# WirelessI2cController.net
KiCad netlist of a schematic drawn in EAGLE
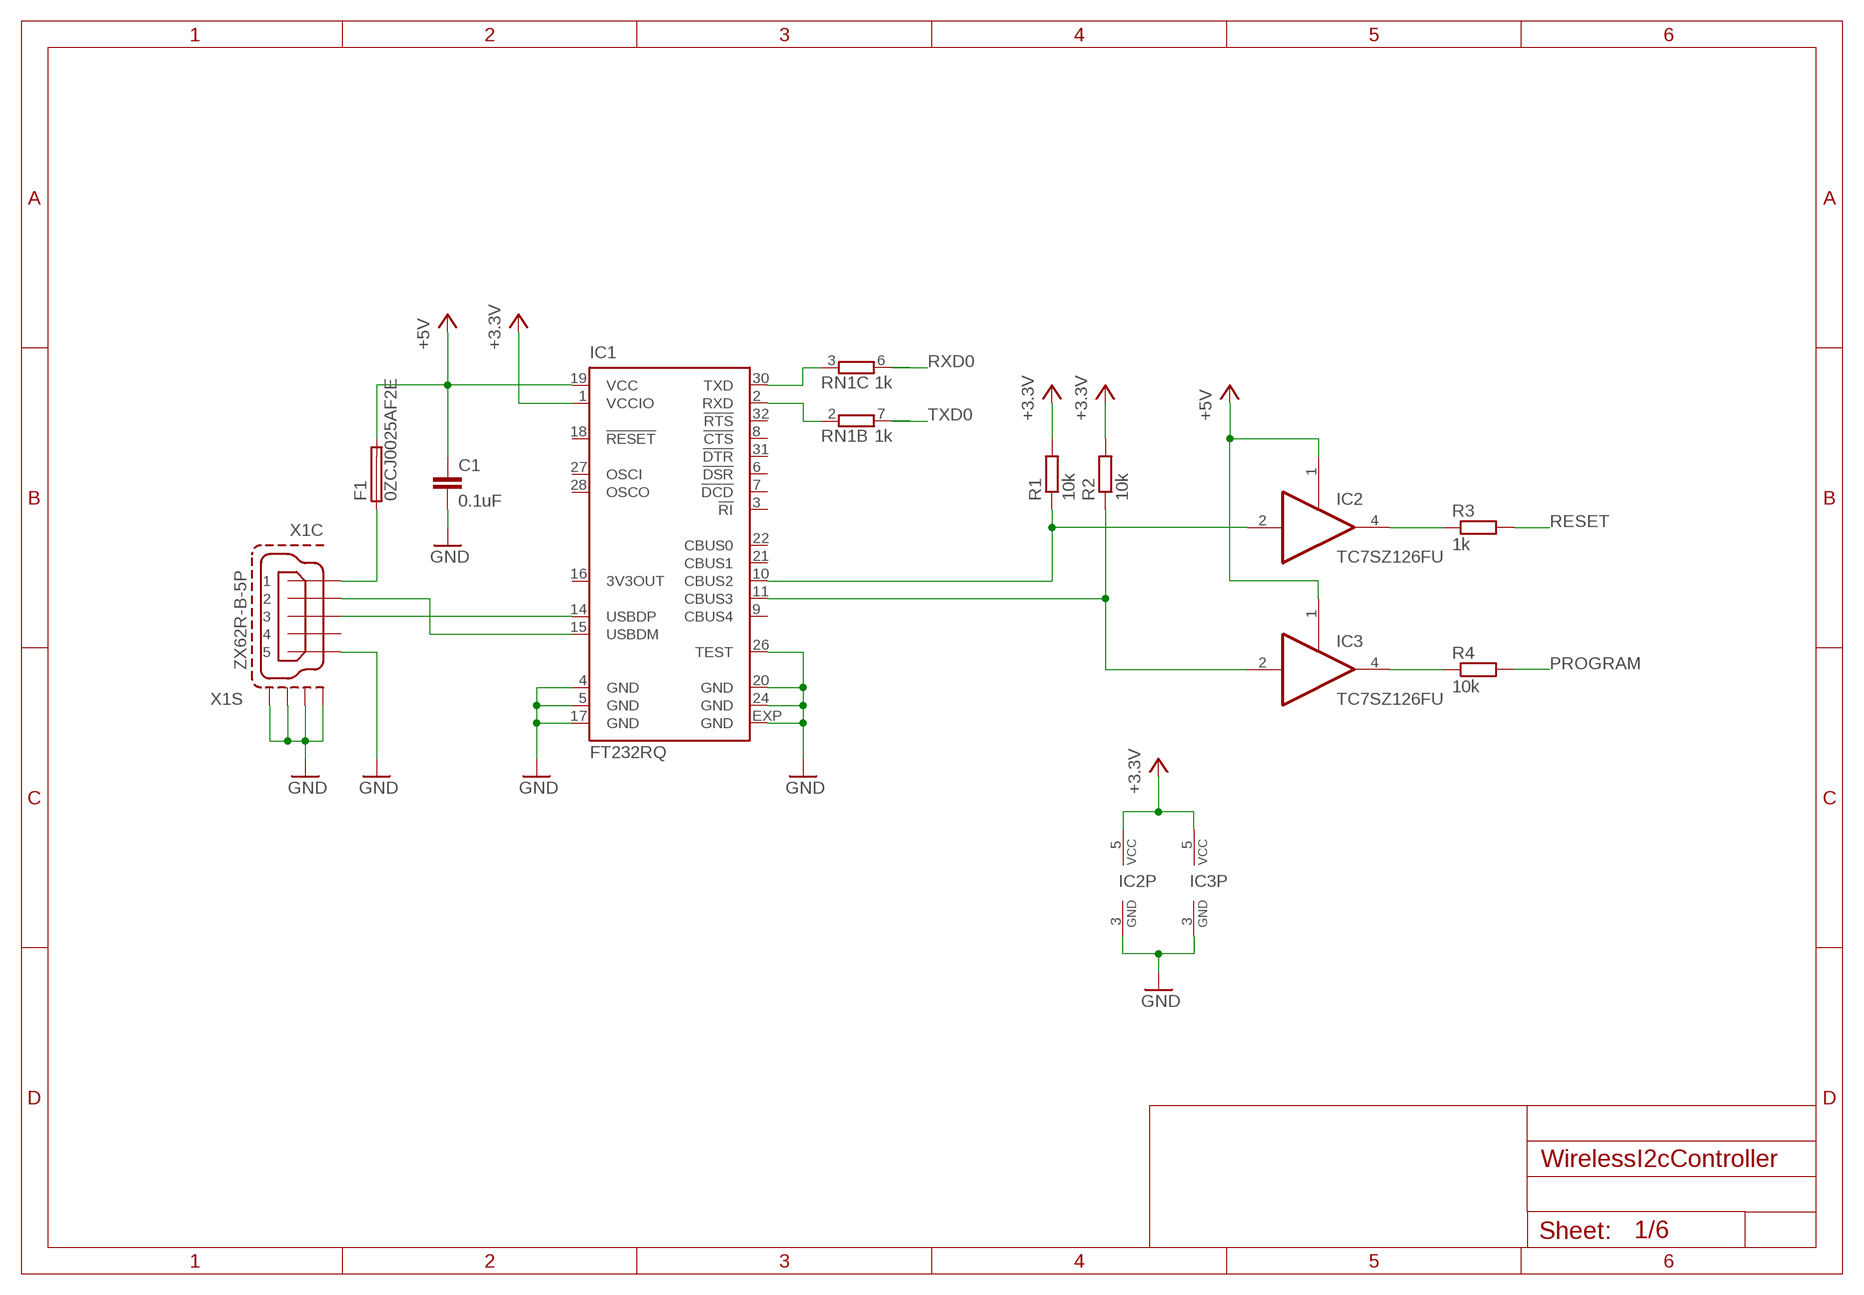
[diagram p0: schematic, sheet 1]
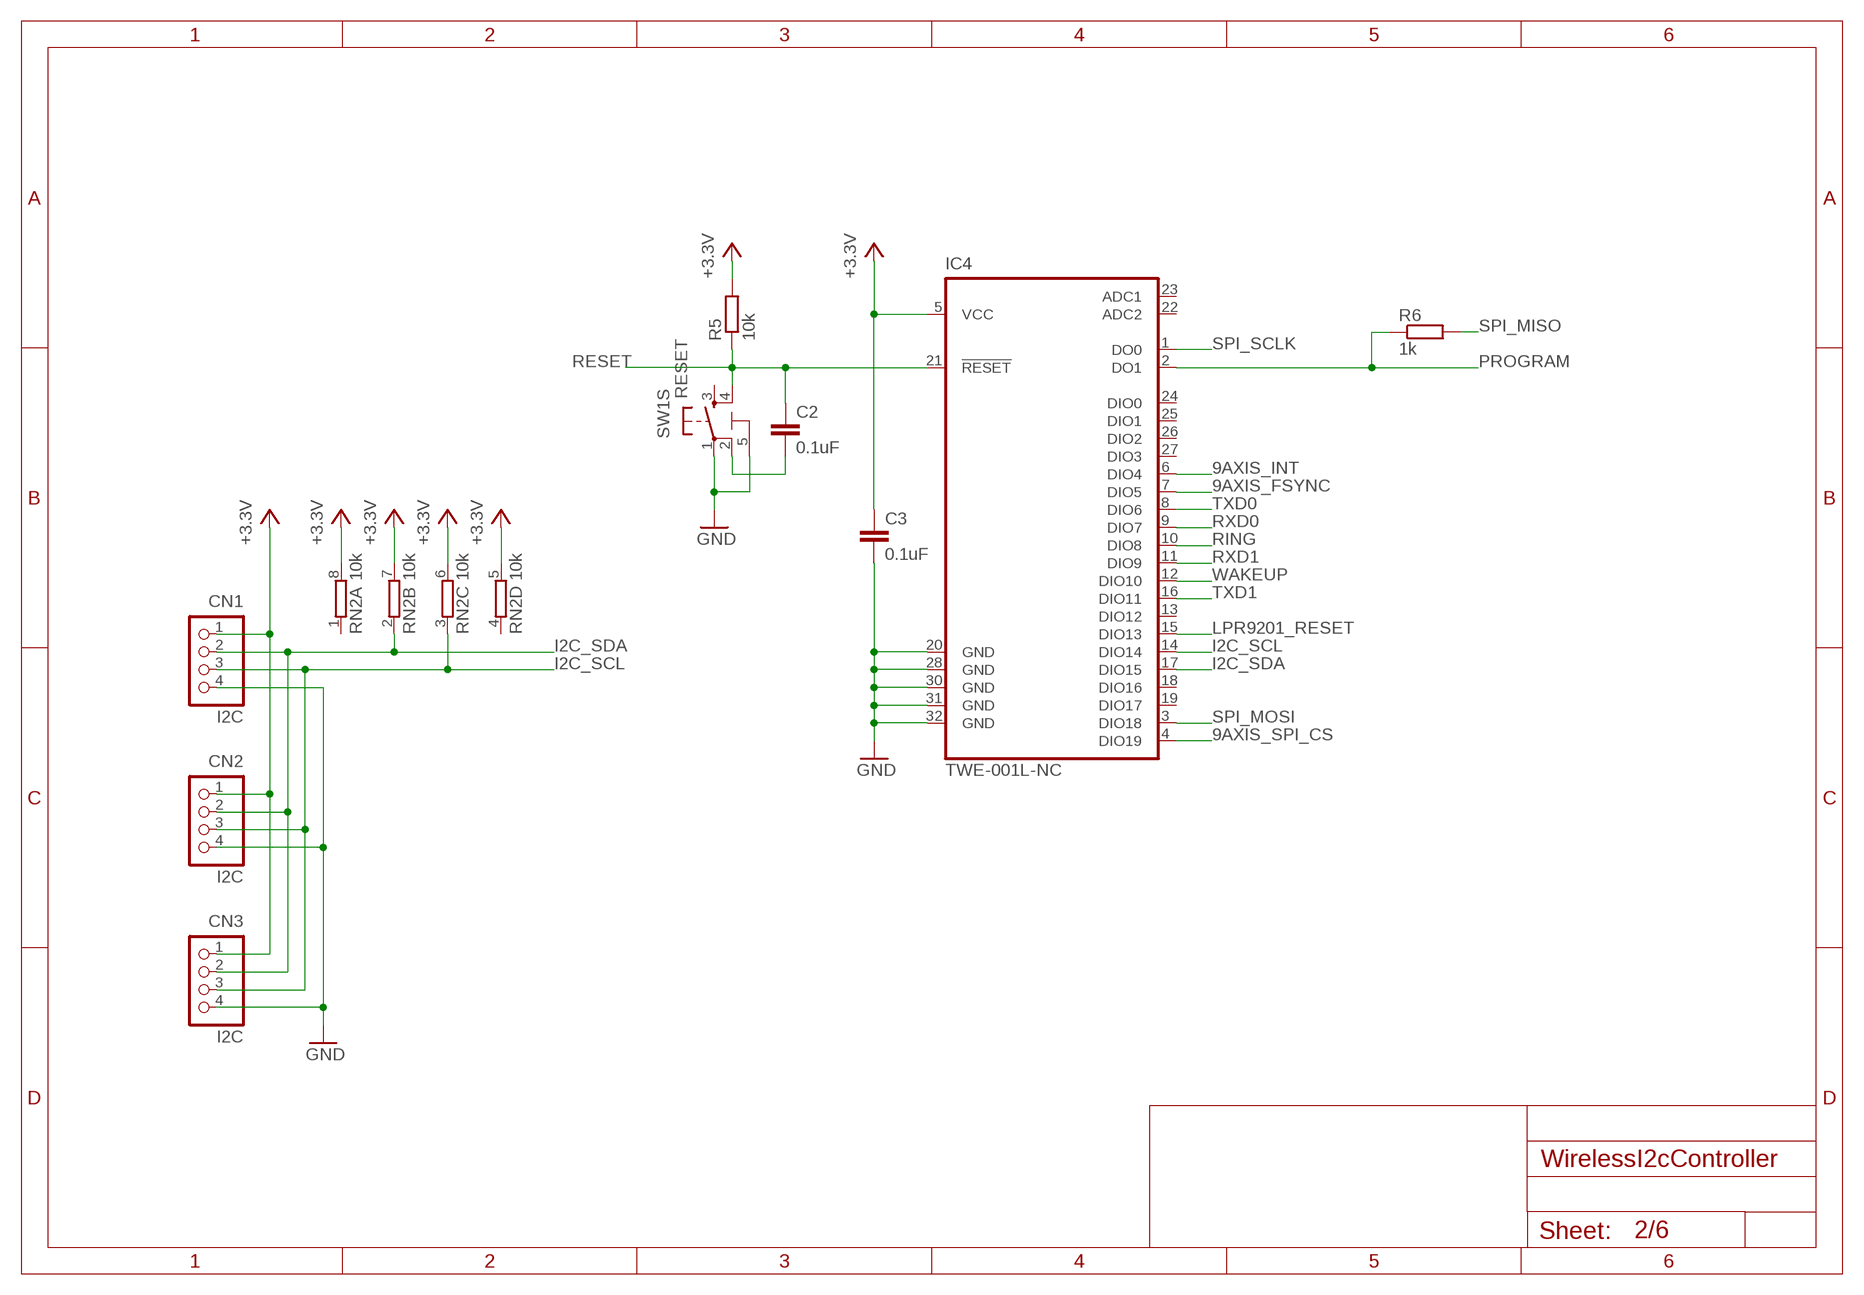
[diagram p1: schematic, sheet 2]
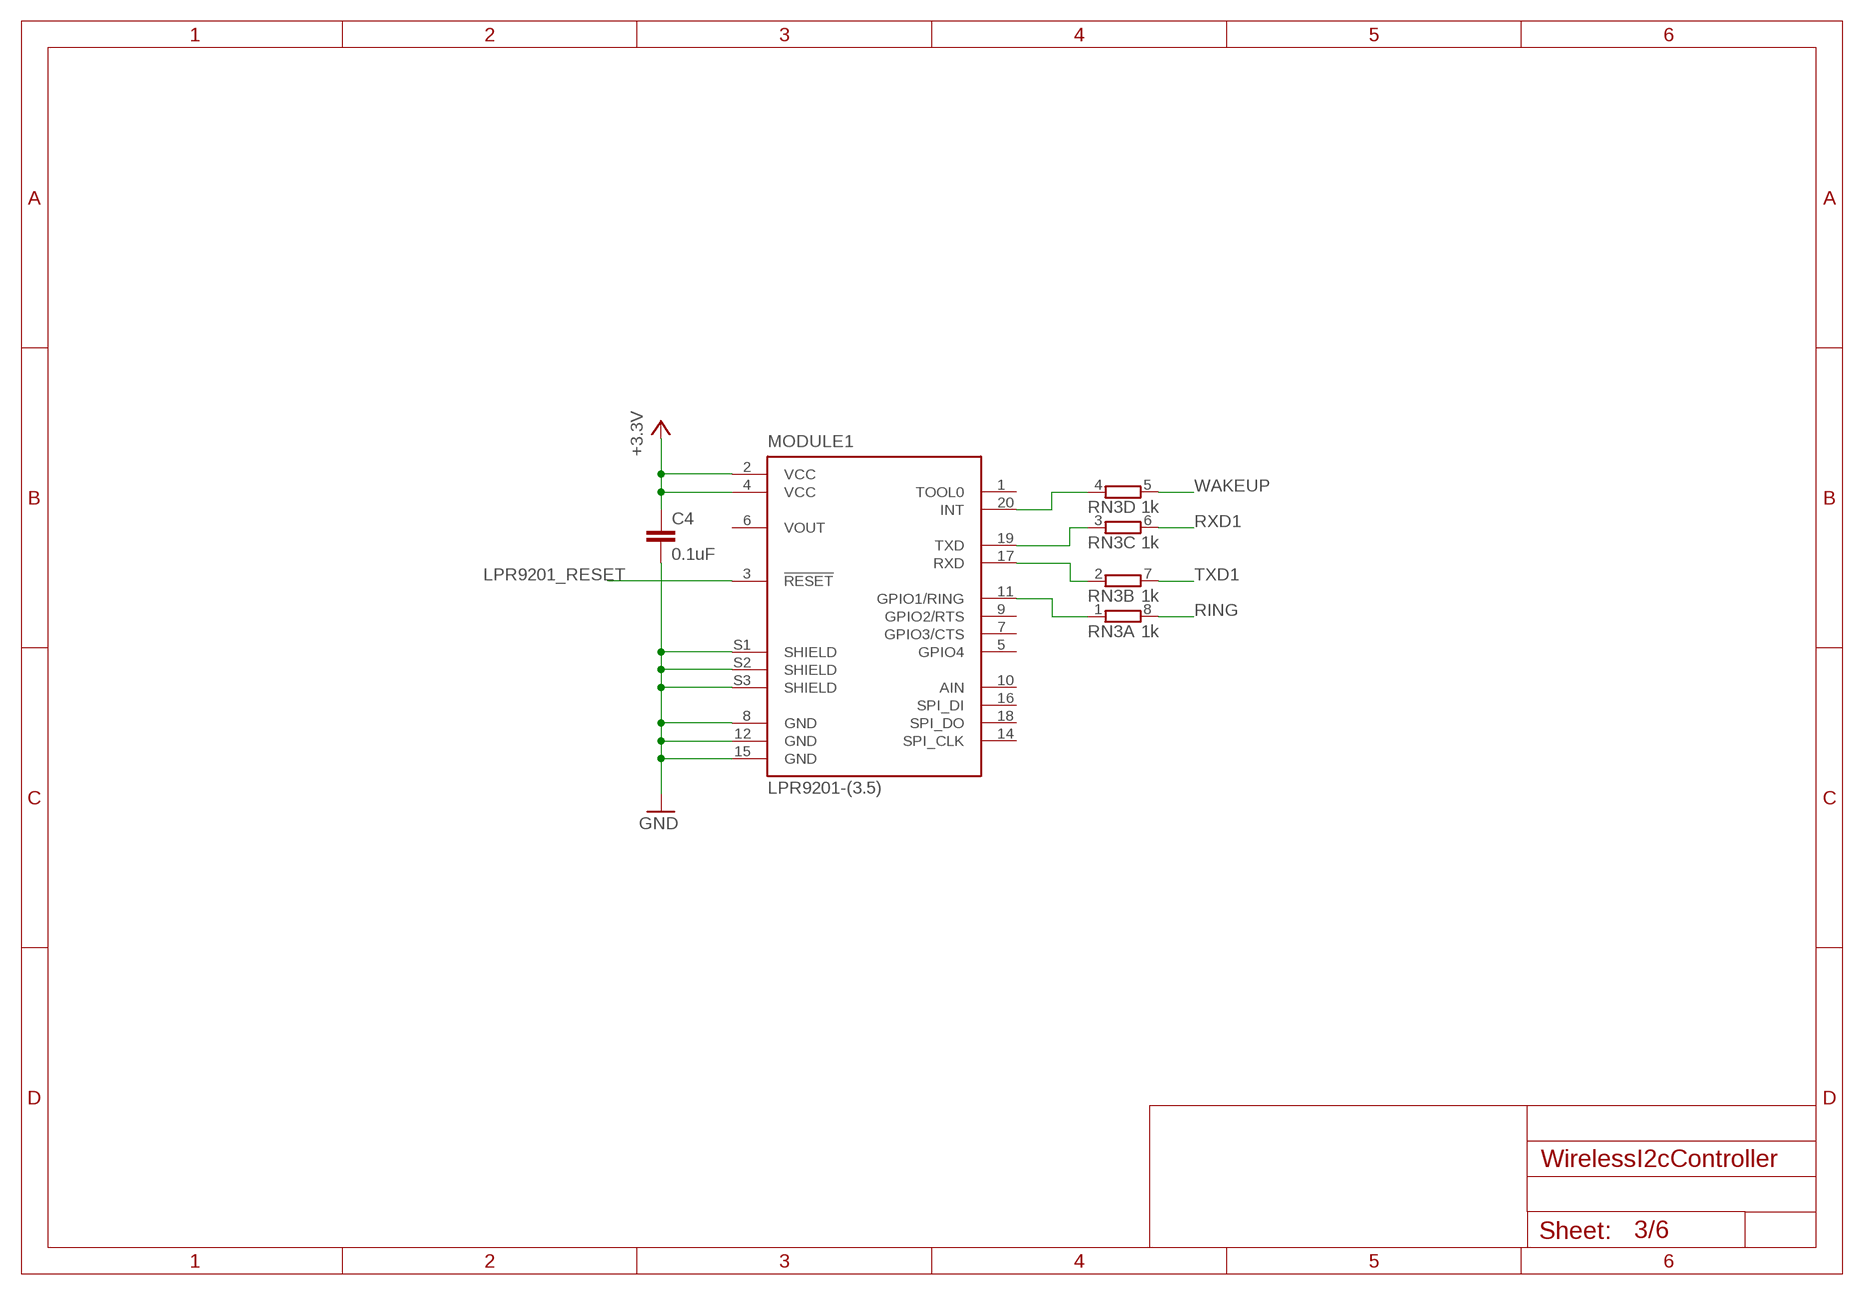
[diagram p2: schematic, sheet 3]
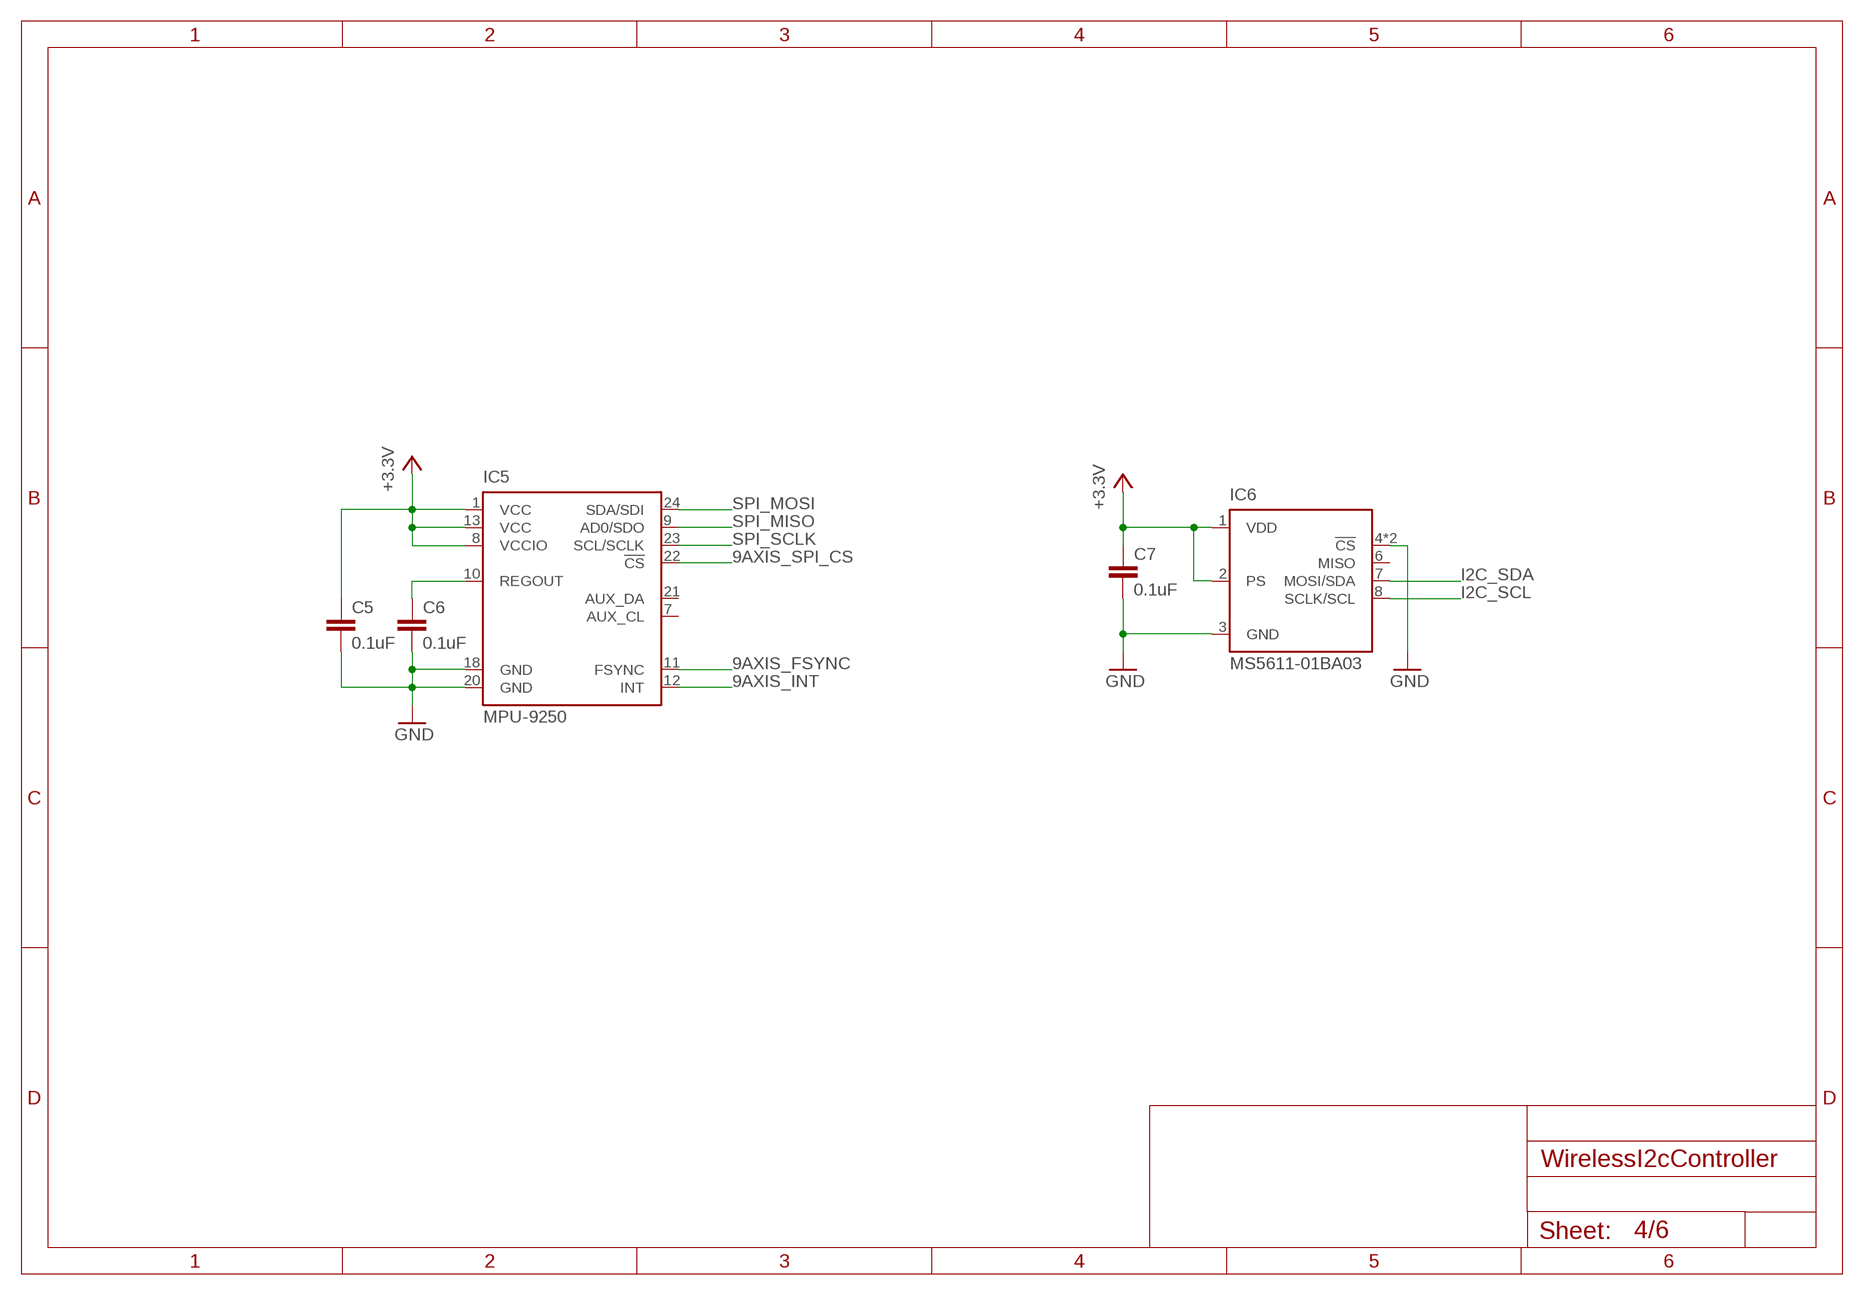
[diagram p3: schematic, sheet 4]
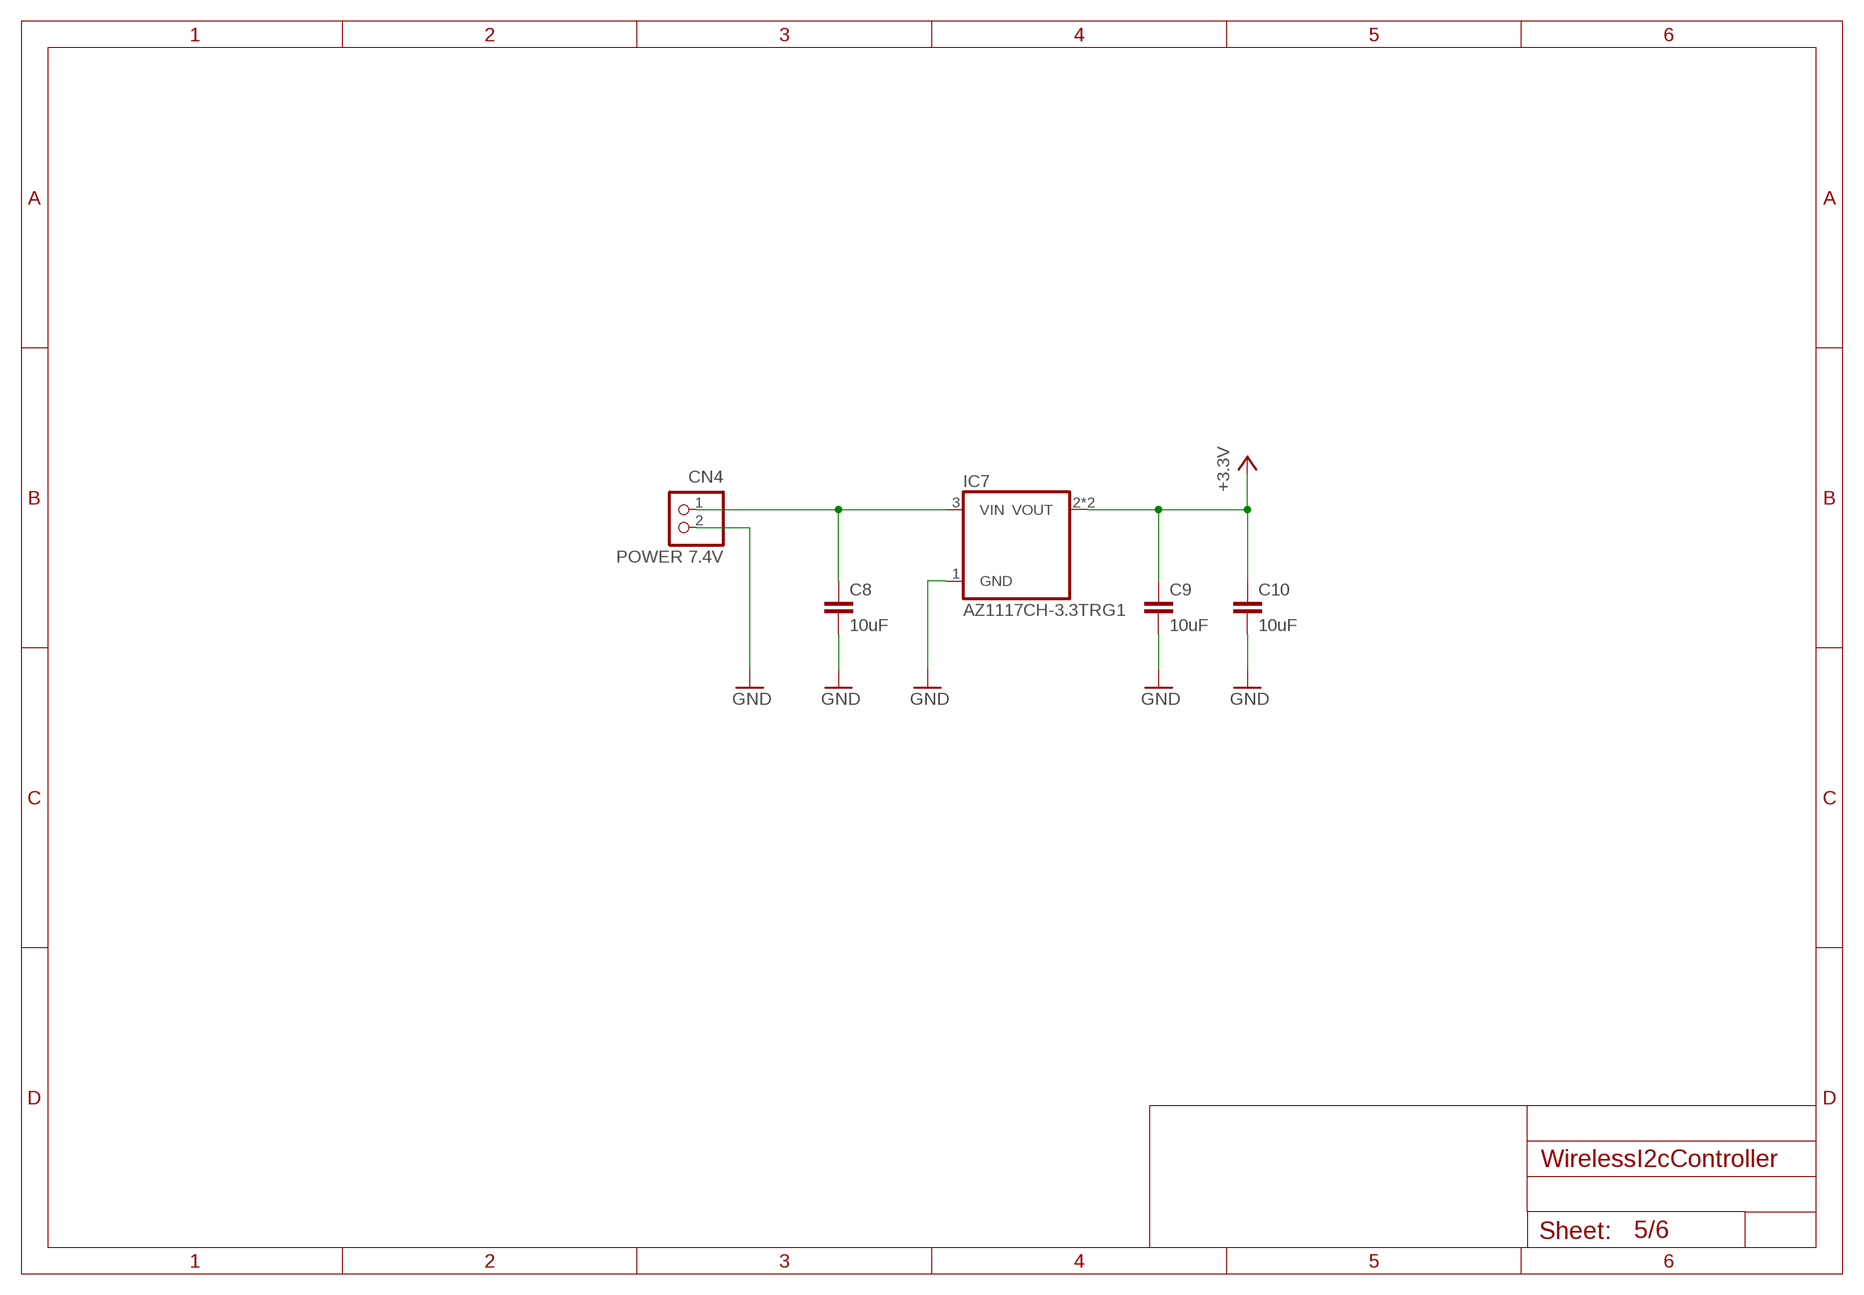
[diagram p4: schematic, sheet 5]
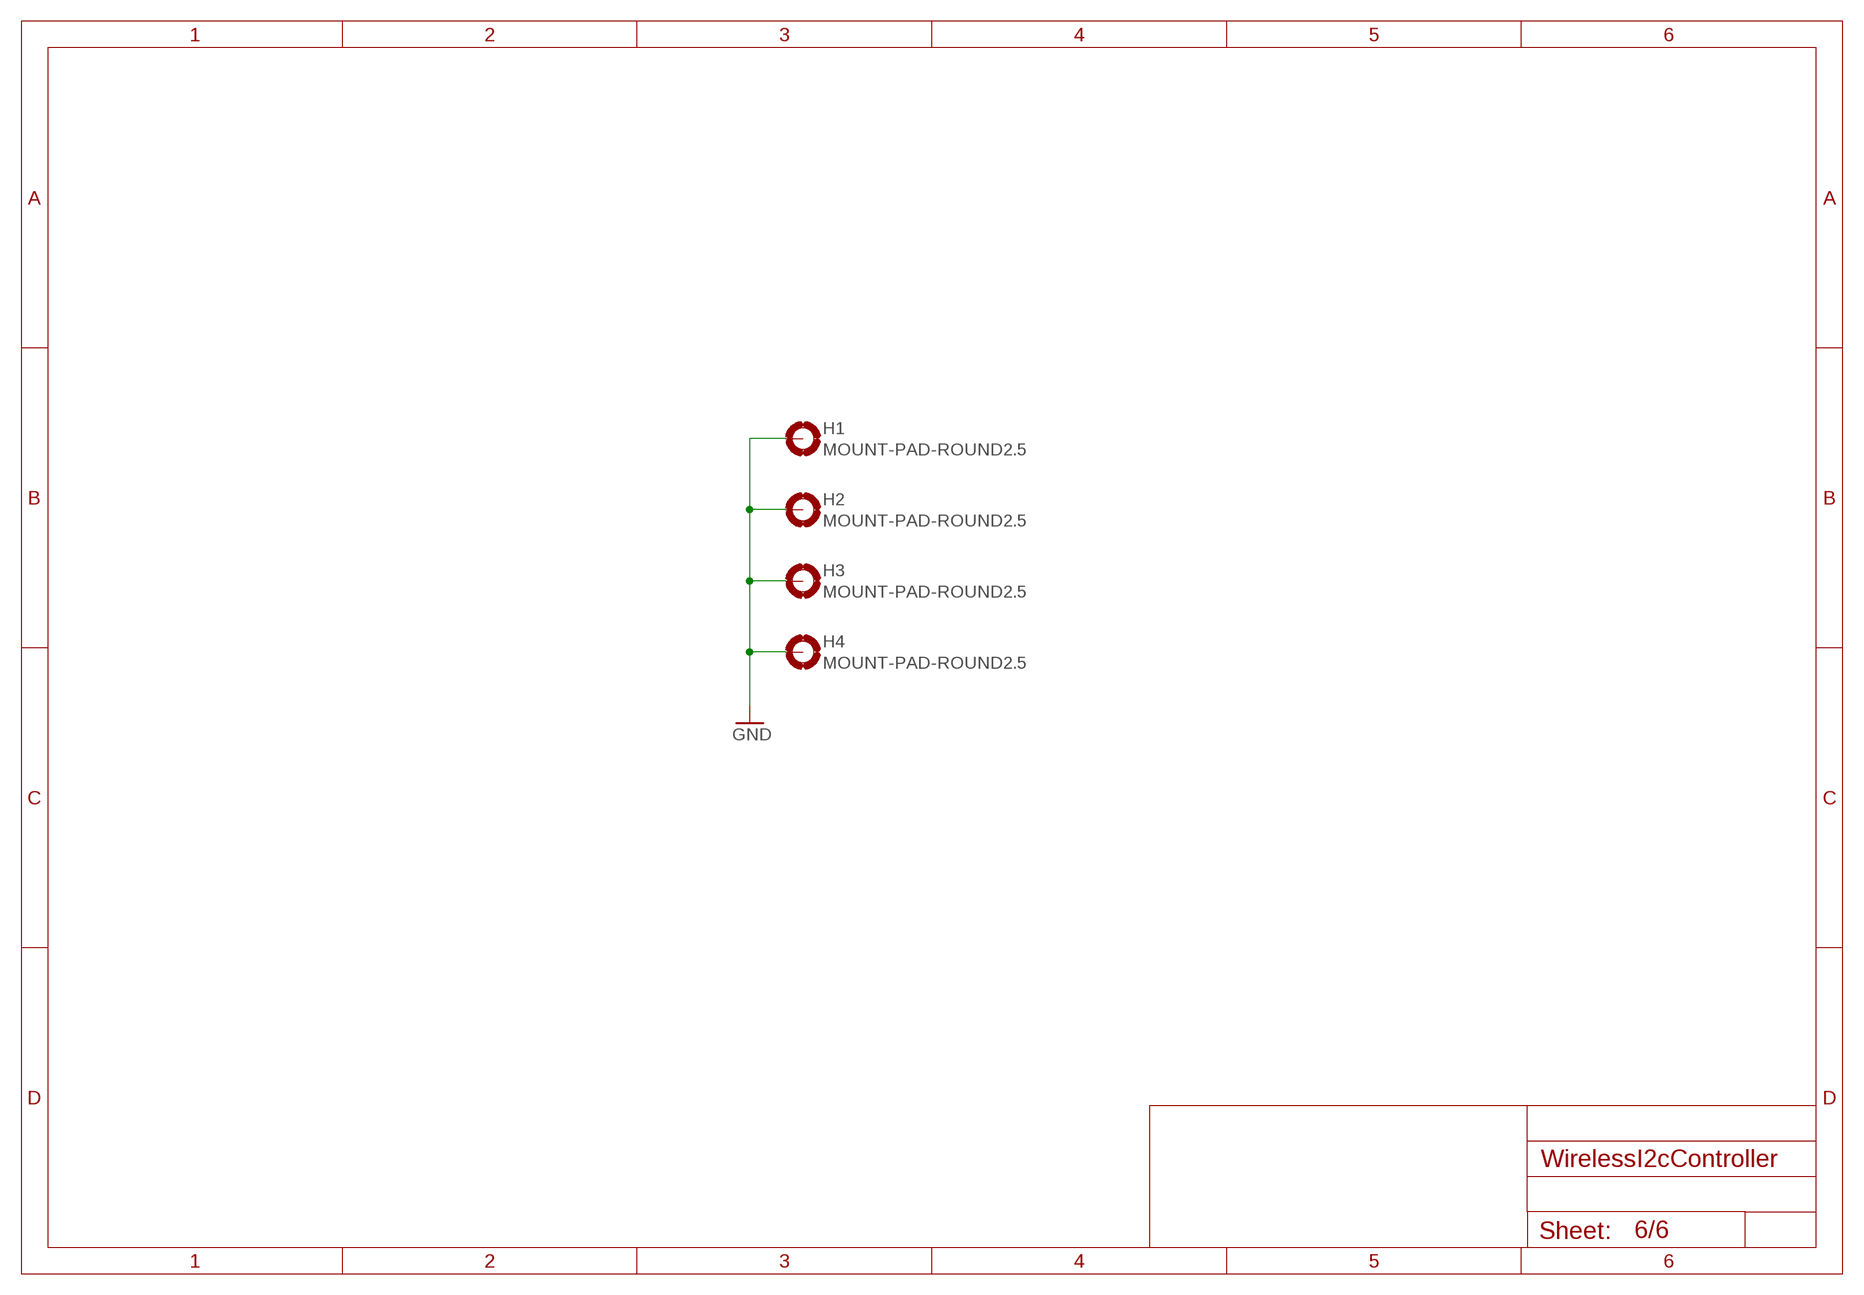
[diagram p5: schematic, sheet 6]

(export (version "E")
  (design (tool "Eeschema 10.0.6"))
  (components
    (comp (ref "C5")
      (value "0.1uF")
      (footprint "eagle-import:C0402")
      (libsource (lib "eagle-import") (part "C-EUC0402"))
    )
    (comp (ref "C6")
      (value "0.1uF")
      (footprint "eagle-import:C0402")
      (libsource (lib "eagle-import") (part "C-EUC0402"))
    )
    (comp (ref "C7")
      (value "0.1uF")
      (footprint "eagle-import:C0402")
      (libsource (lib "eagle-import") (part "C-EUC0402"))
    )
    (comp (ref "IC5")
      (value "MPU-9250")
      (footprint "eagle-import:QFN24-SMALL")
      (libsource (lib "eagle-import") (part "MPU-9250"))
    )
    (comp (ref "IC6")
      (value "MS5611-01BA03")
      (footprint "eagle-import:LGA8")
      (libsource (lib "eagle-import") (part "MS5611-01BA03"))
    )
    (comp (ref "C4")
      (value "0.1uF")
      (footprint "eagle-import:C0402")
      (libsource (lib "eagle-import") (part "C-EUC0402"))
    )
    (comp (ref "MODULE1")
      (value "LPR9201-(3.5)")
      (footprint "eagle-import:DF12(_)-20DP-0.5V")
      (libsource (lib "eagle-import") (part "LPR9201-()3.5"))
    )
    (comp (ref "RN3")
      (value "1k")
      (footprint "eagle-import:EXB38V")
      (libsource (lib "eagle-import") (part "4R-NEXB38V"))
    )
    (comp (ref "C8")
      (value "10uF")
      (footprint "eagle-import:C0805")
      (libsource (lib "eagle-import") (part "C-EUC0805"))
    )
    (comp (ref "C9")
      (value "10uF")
      (footprint "eagle-import:C0805")
      (libsource (lib "eagle-import") (part "C-EUC0805"))
    )
    (comp (ref "C10")
      (value "10uF")
      (footprint "eagle-import:C0805")
      (libsource (lib "eagle-import") (part "C-EUC0805"))
    )
    (comp (ref "CN4")
      (value "POWER 7.4V")
      (footprint "eagle-import:S2B-PH-K-S")
      (libsource (lib "eagle-import") (part "S2B-PH-K-S"))
    )
    (comp (ref "IC7")
      (value "AZ1117CH-3.3TRG1")
      (footprint "eagle-import:SOT223")
      (libsource (lib "eagle-import") (part "AZ1117CH-3.3TRG1"))
    )
    (comp (ref "H1")
      (value "MOUNT-PAD-ROUND2.5")
      (footprint "eagle-import:2,5-PAD")
      (libsource (lib "eagle-import") (part "MOUNT-PAD-ROUND2.5"))
    )
    (comp (ref "H2")
      (value "MOUNT-PAD-ROUND2.5")
      (footprint "eagle-import:2,5-PAD")
      (libsource (lib "eagle-import") (part "MOUNT-PAD-ROUND2.5"))
    )
    (comp (ref "H3")
      (value "MOUNT-PAD-ROUND2.5")
      (footprint "eagle-import:2,5-PAD")
      (libsource (lib "eagle-import") (part "MOUNT-PAD-ROUND2.5"))
    )
    (comp (ref "H4")
      (value "MOUNT-PAD-ROUND2.5")
      (footprint "eagle-import:2,5-PAD")
      (libsource (lib "eagle-import") (part "MOUNT-PAD-ROUND2.5"))
    )
    (comp (ref "C2")
      (value "0.1uF")
      (footprint "eagle-import:C0402")
      (libsource (lib "eagle-import") (part "C-EUC0402"))
    )
    (comp (ref "C3")
      (value "0.1uF")
      (footprint "eagle-import:C0402")
      (libsource (lib "eagle-import") (part "C-EUC0402"))
    )
    (comp (ref "CN1")
      (value "I2C")
      (footprint "eagle-import:B4B-PH-K-S")
      (libsource (lib "eagle-import") (part "B4B-PH-K-S"))
    )
    (comp (ref "CN2")
      (value "I2C")
      (footprint "eagle-import:B4B-PH-K-S")
      (libsource (lib "eagle-import") (part "B4B-PH-K-S"))
    )
    (comp (ref "CN3")
      (value "I2C")
      (footprint "eagle-import:B4B-PH-K-S")
      (libsource (lib "eagle-import") (part "B4B-PH-K-S"))
    )
    (comp (ref "IC4")
      (value "TWE-001L-NC")
      (footprint "eagle-import:QFN32-HOLE")
      (libsource (lib "eagle-import") (part "TWE-001L-NC"))
    )
    (comp (ref "R5")
      (value "10k")
      (footprint "eagle-import:R0402")
      (libsource (lib "eagle-import") (part "R-EU_R0402"))
    )
    (comp (ref "R6")
      (value "1k")
      (footprint "eagle-import:R0402")
      (libsource (lib "eagle-import") (part "R-EU_R0402"))
    )
    (comp (ref "RN2")
      (value "10k")
      (footprint "eagle-import:EXB38V")
      (libsource (lib "eagle-import") (part "4R-NEXB38V"))
    )
    (comp (ref "SW1")
      (value "RESET")
      (footprint "eagle-import:KMR2_G_")
      (libsource (lib "eagle-import") (part "KMR2G41"))
    )
    (comp (ref "C1")
      (value "0.1uF")
      (footprint "eagle-import:C0402")
      (libsource (lib "eagle-import") (part "C-EUC0402"))
    )
    (comp (ref "F1")
      (value "0ZCJ0025AF2E")
      (footprint "eagle-import:0ZCJ")
      (libsource (lib "eagle-import") (part "0ZCJ0025AF2E"))
    )
    (comp (ref "IC1")
      (value "FT232RQ")
      (footprint "eagle-import:QFN32")
      (libsource (lib "eagle-import") (part "FT232RQ"))
    )
    (comp (ref "IC2")
      (value "TC7SZ126FU")
      (footprint "eagle-import:SC70-5")
      (libsource (lib "eagle-import") (part "741G126DCKLVC"))
    )
    (comp (ref "IC3")
      (value "TC7SZ126FU")
      (footprint "eagle-import:SC70-5")
      (libsource (lib "eagle-import") (part "741G126DCKLVC"))
    )
    (comp (ref "R1")
      (value "10k")
      (footprint "eagle-import:R0402")
      (libsource (lib "eagle-import") (part "R-EU_R0402"))
    )
    (comp (ref "R2")
      (value "10k")
      (footprint "eagle-import:R0402")
      (libsource (lib "eagle-import") (part "R-EU_R0402"))
    )
    (comp (ref "R3")
      (value "1k")
      (footprint "eagle-import:R0402")
      (libsource (lib "eagle-import") (part "R-EU_R0402"))
    )
    (comp (ref "R4")
      (value "10k")
      (footprint "eagle-import:R0402")
      (libsource (lib "eagle-import") (part "R-EU_R0402"))
    )
    (comp (ref "RN1")
      (value "1k")
      (footprint "eagle-import:EXB38V")
      (libsource (lib "eagle-import") (part "4R-NEXB38V"))
    )
    (comp (ref "X1")
      (value "ZX62R-B-5P")
      (footprint "eagle-import:ZX62R-B-5P")
      (libsource (lib "eagle-import") (part "ZX62R-B-5P"))
    )
  )
  (nets
    (net (code "1") (name "+3.3V") (class "Default")
      (node (ref "C10") (pin "1") (pinfunction "1_1") (pintype "passive"))
      (node (ref "C3") (pin "1") (pinfunction "1_1") (pintype "passive"))
      (node (ref "C4") (pin "1") (pinfunction "1_1") (pintype "passive"))
      (node (ref "C5") (pin "1") (pinfunction "1_1") (pintype "passive"))
      (node (ref "C7") (pin "1") (pinfunction "1_1") (pintype "passive"))
      (node (ref "C9") (pin "1") (pinfunction "1_1") (pintype "passive"))
      (node (ref "CN1") (pin "1") (pinfunction "1_1") (pintype "passive"))
      (node (ref "CN2") (pin "1") (pinfunction "1_1") (pintype "passive"))
      (node (ref "CN3") (pin "1") (pinfunction "1_1") (pintype "passive"))
      (node (ref "IC1") (pin "1") (pinfunction "VCCIO_1") (pintype "power_in"))
      (node (ref "IC2") (pin "5") (pinfunction "VCC_5") (pintype "power_in"))
      (node (ref "IC3") (pin "5") (pinfunction "VCC_5") (pintype "power_in"))
      (node (ref "IC4") (pin "5") (pinfunction "VCC_5") (pintype "power_in"))
      (node (ref "IC5") (pin "1") (pinfunction "VCC_1") (pintype "power_in"))
      (node (ref "IC5") (pin "13") (pinfunction "VCC_13") (pintype "power_in"))
      (node (ref "IC5") (pin "8") (pinfunction "VCCIO_8") (pintype "power_in"))
      (node (ref "IC6") (pin "1") (pinfunction "VDD_1") (pintype "power_in"))
      (node (ref "IC6") (pin "2") (pinfunction "PS_2") (pintype "input"))
      (node (ref "IC7") (pin "2") (pinfunction "VOUT_2") (pintype "passive"))
      (node (ref "IC7") (pin "4") (pinfunction "VOUT_4") (pintype "passive"))
      (node (ref "MODULE1") (pin "2") (pinfunction "VCC_2") (pintype "power_in"))
      (node (ref "MODULE1") (pin "4") (pinfunction "VCC_4") (pintype "power_in"))
      (node (ref "R1") (pin "2") (pinfunction "2_2") (pintype "passive"))
      (node (ref "R2") (pin "2") (pinfunction "2_2") (pintype "passive"))
      (node (ref "R5") (pin "2") (pinfunction "2_2") (pintype "passive"))
      (node (ref "RN2") (pin "5") (pinfunction "2_5") (pintype "passive"))
      (node (ref "RN2") (pin "6") (pinfunction "2_6") (pintype "passive"))
      (node (ref "RN2") (pin "7") (pinfunction "2_7") (pintype "passive"))
      (node (ref "RN2") (pin "8") (pinfunction "2_8") (pintype "passive"))
    )
    (net (code "2") (name "+5V") (class "Default")
      (node (ref "C1") (pin "1") (pinfunction "1_1") (pintype "passive"))
      (node (ref "F1") (pin "2") (pinfunction "2_2") (pintype "passive"))
      (node (ref "IC1") (pin "19") (pinfunction "VCC_19") (pintype "power_in"))
      (node (ref "IC2") (pin "1") (pinfunction "OE_1") (pintype "input"))
      (node (ref "IC3") (pin "1") (pinfunction "OE_1") (pintype "input"))
    )
    (net (code "3") (name "3V3OUT") (class "Default")
      (node (ref "IC1") (pin "16") (pinfunction "3V3OUT_16") (pintype "power_in"))
    )
    (net (code "4") (name "9AXIS_FSYNC") (class "Default")
      (node (ref "IC4") (pin "7") (pinfunction "DIO5_7") (pintype "bidirectional"))
      (node (ref "IC5") (pin "11") (pinfunction "FSYNC_11") (pintype "input"))
    )
    (net (code "5") (name "9AXIS_INT") (class "Default")
      (node (ref "IC4") (pin "6") (pinfunction "DIO4_6") (pintype "bidirectional"))
      (node (ref "IC5") (pin "12") (pinfunction "INT_12") (pintype "output"))
    )
    (net (code "6") (name "9AXIS_SPI_CS") (class "Default")
      (node (ref "IC4") (pin "4") (pinfunction "DIO19_4") (pintype "bidirectional"))
      (node (ref "IC5") (pin "22") (pinfunction "~{CS}_22") (pintype "input"))
    )
    (net (code "7") (name "GND") (class "Default")
      (node (ref "C1") (pin "2") (pinfunction "2_2") (pintype "passive"))
      (node (ref "C10") (pin "2") (pinfunction "2_2") (pintype "passive"))
      (node (ref "C3") (pin "2") (pinfunction "2_2") (pintype "passive"))
      (node (ref "C4") (pin "2") (pinfunction "2_2") (pintype "passive"))
      (node (ref "C5") (pin "2") (pinfunction "2_2") (pintype "passive"))
      (node (ref "C6") (pin "2") (pinfunction "2_2") (pintype "passive"))
      (node (ref "C7") (pin "2") (pinfunction "2_2") (pintype "passive"))
      (node (ref "C8") (pin "2") (pinfunction "2_2") (pintype "passive"))
      (node (ref "C9") (pin "2") (pinfunction "2_2") (pintype "passive"))
      (node (ref "CN1") (pin "4") (pinfunction "4_4") (pintype "passive"))
      (node (ref "CN2") (pin "4") (pinfunction "4_4") (pintype "passive"))
      (node (ref "CN3") (pin "4") (pinfunction "4_4") (pintype "passive"))
      (node (ref "CN4") (pin "2") (pinfunction "2_2") (pintype "passive"))
      (node (ref "H1") (pin "B2,5") (pinfunction "MOUNT_B2,5") (pintype "passive"))
      (node (ref "H2") (pin "B2,5") (pinfunction "MOUNT_B2,5") (pintype "passive"))
      (node (ref "H3") (pin "B2,5") (pinfunction "MOUNT_B2,5") (pintype "passive"))
      (node (ref "H4") (pin "B2,5") (pinfunction "MOUNT_B2,5") (pintype "passive"))
      (node (ref "IC1") (pin "17") (pinfunction "GND_17") (pintype "power_in"))
      (node (ref "IC1") (pin "20") (pinfunction "GND_20") (pintype "power_in"))
      (node (ref "IC1") (pin "24") (pinfunction "GND_24") (pintype "power_in"))
      (node (ref "IC1") (pin "26") (pinfunction "TEST_26") (pintype "input"))
      (node (ref "IC1") (pin "4") (pinfunction "GND_4") (pintype "power_in"))
      (node (ref "IC1") (pin "5") (pinfunction "GND_5") (pintype "power_in"))
      (node (ref "IC1") (pin "EXP") (pinfunction "GND_EXP") (pintype "power_in"))
      (node (ref "IC2") (pin "3") (pinfunction "GND_3") (pintype "power_in"))
      (node (ref "IC3") (pin "3") (pinfunction "GND_3") (pintype "power_in"))
      (node (ref "IC4") (pin "20") (pinfunction "GND_20") (pintype "power_in"))
      (node (ref "IC4") (pin "28") (pinfunction "GND_28") (pintype "power_in"))
      (node (ref "IC4") (pin "30") (pinfunction "GND_30") (pintype "power_in"))
      (node (ref "IC4") (pin "31") (pinfunction "GND_31") (pintype "power_in"))
      (node (ref "IC4") (pin "32") (pinfunction "GND_32") (pintype "power_in"))
      (node (ref "IC5") (pin "18") (pinfunction "GND_18") (pintype "power_in"))
      (node (ref "IC5") (pin "20") (pinfunction "GND_20") (pintype "power_in"))
      (node (ref "IC6") (pin "3") (pinfunction "GND_3") (pintype "power_in"))
      (node (ref "IC6") (pin "4") (pinfunction "~{CS}_4") (pintype "input"))
      (node (ref "IC6") (pin "5") (pinfunction "~{CS}_5") (pintype "input"))
      (node (ref "IC7") (pin "1") (pinfunction "GND_1") (pintype "power_in"))
      (node (ref "MODULE1") (pin "12") (pinfunction "GND_12") (pintype "power_in"))
      (node (ref "MODULE1") (pin "15") (pinfunction "GND_15") (pintype "power_in"))
      (node (ref "MODULE1") (pin "8") (pinfunction "GND_8") (pintype "power_in"))
      (node (ref "MODULE1") (pin "S1") (pinfunction "SHIELD_S1") (pintype "passive"))
      (node (ref "MODULE1") (pin "S2") (pinfunction "SHIELD_S2") (pintype "passive"))
      (node (ref "MODULE1") (pin "S3") (pinfunction "SHIELD_S3") (pintype "passive"))
      (node (ref "SW1") (pin "1") (pinfunction "P_1") (pintype "passive"))
      (node (ref "SW1") (pin "5") (pinfunction "5_5") (pintype "passive"))
      (node (ref "X1") (pin "5") (pinfunction "5_5") (pintype "power_in"))
      (node (ref "X1") (pin "S1") (pinfunction "S1_S1") (pintype "passive"))
      (node (ref "X1") (pin "S2") (pinfunction "S2_S2") (pintype "passive"))
      (node (ref "X1") (pin "S3") (pinfunction "S3_S3") (pintype "passive"))
      (node (ref "X1") (pin "S4") (pinfunction "S4_S4") (pintype "passive"))
    )
    (net (code "8") (name "I2C_SCL") (class "Default")
      (node (ref "CN1") (pin "3") (pinfunction "3_3") (pintype "passive"))
      (node (ref "CN2") (pin "3") (pinfunction "3_3") (pintype "passive"))
      (node (ref "CN3") (pin "3") (pinfunction "3_3") (pintype "passive"))
      (node (ref "IC4") (pin "14") (pinfunction "DIO14_14") (pintype "bidirectional"))
      (node (ref "IC6") (pin "8") (pinfunction "SCLK/SCL_8") (pintype "input"))
      (node (ref "RN2") (pin "3") (pinfunction "1_3") (pintype "passive"))
    )
    (net (code "9") (name "I2C_SDA") (class "Default")
      (node (ref "CN1") (pin "2") (pinfunction "2_2") (pintype "passive"))
      (node (ref "CN2") (pin "2") (pinfunction "2_2") (pintype "passive"))
      (node (ref "CN3") (pin "2") (pinfunction "2_2") (pintype "passive"))
      (node (ref "IC4") (pin "17") (pinfunction "DIO15_17") (pintype "bidirectional"))
      (node (ref "IC6") (pin "7") (pinfunction "MOSI/SDA_7") (pintype "bidirectional"))
      (node (ref "RN2") (pin "2") (pinfunction "1_2") (pintype "passive"))
    )
    (net (code "10") (name "LPR9201_RESET") (class "Default")
      (node (ref "IC4") (pin "15") (pinfunction "DIO13_15") (pintype "bidirectional"))
      (node (ref "MODULE1") (pin "3") (pinfunction "~{RESET}_3") (pintype "bidirectional"))
    )
    (net (code "11") (name "Net-(F1-Pad1)") (class "Default")
      (node (ref "F1") (pin "1") (pinfunction "1_1") (pintype "passive"))
      (node (ref "X1") (pin "1") (pinfunction "1_1") (pintype "power_in"))
    )
    (net (code "12") (name "Net-(IC1-CBUS2)") (class "Default")
      (node (ref "IC1") (pin "10") (pinfunction "CBUS2_10") (pintype "bidirectional"))
      (node (ref "IC2") (pin "2") (pinfunction "I_2") (pintype "input"))
      (node (ref "R1") (pin "1") (pinfunction "1_1") (pintype "passive"))
    )
    (net (code "13") (name "Net-(IC1-CBUS3)") (class "Default")
      (node (ref "IC1") (pin "11") (pinfunction "CBUS3_11") (pintype "bidirectional"))
      (node (ref "IC3") (pin "2") (pinfunction "I_2") (pintype "input"))
      (node (ref "R2") (pin "1") (pinfunction "1_1") (pintype "passive"))
    )
    (net (code "14") (name "Net-(IC1-RXD)") (class "Default")
      (node (ref "IC1") (pin "2") (pinfunction "RXD_2") (pintype "input"))
      (node (ref "RN1") (pin "2") (pinfunction "1_2") (pintype "passive"))
    )
    (net (code "15") (name "Net-(IC1-TXD)") (class "Default")
      (node (ref "IC1") (pin "30") (pinfunction "TXD_30") (pintype "output"))
      (node (ref "RN1") (pin "3") (pinfunction "1_3") (pintype "passive"))
    )
    (net (code "16") (name "Net-(IC1-USBDM)") (class "Default")
      (node (ref "IC1") (pin "15") (pinfunction "USBDM_15") (pintype "bidirectional"))
      (node (ref "X1") (pin "2") (pinfunction "2_2") (pintype "output"))
    )
    (net (code "17") (name "Net-(IC1-USBDP)") (class "Default")
      (node (ref "IC1") (pin "14") (pinfunction "USBDP_14") (pintype "bidirectional"))
      (node (ref "X1") (pin "3") (pinfunction "3_3") (pintype "bidirectional"))
    )
    (net (code "18") (name "Net-(IC2A-O)") (class "Default")
      (node (ref "IC2") (pin "4") (pinfunction "O_4") (pintype "output"))
      (node (ref "R3") (pin "1") (pinfunction "1_1") (pintype "passive"))
    )
    (net (code "19") (name "Net-(IC3A-O)") (class "Default")
      (node (ref "IC3") (pin "4") (pinfunction "O_4") (pintype "output"))
      (node (ref "R4") (pin "1") (pinfunction "1_1") (pintype "passive"))
    )
    (net (code "20") (name "Net-(IC5-REGOUT)") (class "Default")
      (node (ref "C6") (pin "1") (pinfunction "1_1") (pintype "passive"))
      (node (ref "IC5") (pin "10") (pinfunction "REGOUT_10") (pintype "input"))
    )
    (net (code "21") (name "Net-(IC7-VIN)") (class "Default")
      (node (ref "C8") (pin "1") (pinfunction "1_1") (pintype "passive"))
      (node (ref "CN4") (pin "1") (pinfunction "1_1") (pintype "passive"))
      (node (ref "IC7") (pin "3") (pinfunction "VIN_3") (pintype "input"))
    )
    (net (code "22") (name "Net-(MODULE1-GPIO1{slash}RING)") (class "Default")
      (node (ref "MODULE1") (pin "11") (pinfunction "GPIO1/RING_11") (pintype "bidirectional"))
      (node (ref "RN3") (pin "1") (pinfunction "1_1") (pintype "passive"))
    )
    (net (code "23") (name "Net-(MODULE1-INT)") (class "Default")
      (node (ref "MODULE1") (pin "20") (pinfunction "INT_20") (pintype "input"))
      (node (ref "RN3") (pin "4") (pinfunction "1_4") (pintype "passive"))
    )
    (net (code "24") (name "Net-(MODULE1-RXD)") (class "Default")
      (node (ref "MODULE1") (pin "17") (pinfunction "RXD_17") (pintype "input"))
      (node (ref "RN3") (pin "2") (pinfunction "1_2") (pintype "passive"))
    )
    (net (code "25") (name "Net-(MODULE1-TXD)") (class "Default")
      (node (ref "MODULE1") (pin "19") (pinfunction "TXD_19") (pintype "output"))
      (node (ref "RN3") (pin "3") (pinfunction "1_3") (pintype "passive"))
    )
    (net (code "26") (name "Net-(SW1B-P1)") (class "Default")
      (node (ref "C2") (pin "2") (pinfunction "2_2") (pintype "passive"))
      (node (ref "SW1") (pin "2") (pinfunction "P1_2") (pintype "passive"))
    )
    (net (code "27") (name "PROGRAM") (class "Default")
      (node (ref "IC4") (pin "2") (pinfunction "DO1_2") (pintype "output"))
      (node (ref "R4") (pin "2") (pinfunction "2_2") (pintype "passive"))
      (node (ref "R6") (pin "1") (pinfunction "1_1") (pintype "passive"))
    )
    (net (code "28") (name "RESET") (class "Default")
      (node (ref "C2") (pin "1") (pinfunction "1_1") (pintype "passive"))
      (node (ref "IC4") (pin "21") (pinfunction "~{RESET}_21") (pintype "input"))
      (node (ref "R3") (pin "2") (pinfunction "2_2") (pintype "passive"))
      (node (ref "R5") (pin "1") (pinfunction "1_1") (pintype "passive"))
      (node (ref "SW1") (pin "4") (pinfunction "S1_4") (pintype "passive"))
    )
    (net (code "29") (name "RING") (class "Default")
      (node (ref "IC4") (pin "10") (pinfunction "DIO8_10") (pintype "bidirectional"))
      (node (ref "RN3") (pin "8") (pinfunction "2_8") (pintype "passive"))
    )
    (net (code "30") (name "RXD0") (class "Default")
      (node (ref "IC4") (pin "9") (pinfunction "DIO7_9") (pintype "bidirectional"))
      (node (ref "RN1") (pin "6") (pinfunction "2_6") (pintype "passive"))
    )
    (net (code "31") (name "RXD1") (class "Default")
      (node (ref "IC4") (pin "11") (pinfunction "DIO9_11") (pintype "bidirectional"))
      (node (ref "RN3") (pin "6") (pinfunction "2_6") (pintype "passive"))
    )
    (net (code "32") (name "SPI_MISO") (class "Default")
      (node (ref "IC5") (pin "9") (pinfunction "AD0/SDO_9") (pintype "input"))
      (node (ref "R6") (pin "2") (pinfunction "2_2") (pintype "passive"))
    )
    (net (code "33") (name "SPI_MOSI") (class "Default")
      (node (ref "IC4") (pin "3") (pinfunction "DIO18_3") (pintype "bidirectional"))
      (node (ref "IC5") (pin "24") (pinfunction "SDA/SDI_24") (pintype "output"))
    )
    (net (code "34") (name "SPI_SCLK") (class "Default")
      (node (ref "IC4") (pin "1") (pinfunction "DO0_1") (pintype "output"))
      (node (ref "IC5") (pin "23") (pinfunction "SCL/SCLK_23") (pintype "bidirectional"))
    )
    (net (code "35") (name "TXD0") (class "Default")
      (node (ref "IC4") (pin "8") (pinfunction "DIO6_8") (pintype "bidirectional"))
      (node (ref "RN1") (pin "7") (pinfunction "2_7") (pintype "passive"))
    )
    (net (code "36") (name "TXD1") (class "Default")
      (node (ref "IC4") (pin "16") (pinfunction "DIO11_16") (pintype "bidirectional"))
      (node (ref "RN3") (pin "7") (pinfunction "2_7") (pintype "passive"))
    )
    (net (code "37") (name "VOUT") (class "Default")
      (node (ref "MODULE1") (pin "6") (pinfunction "VOUT_6") (pintype "power_in"))
    )
    (net (code "38") (name "WAKEUP") (class "Default")
      (node (ref "IC4") (pin "12") (pinfunction "DIO10_12") (pintype "bidirectional"))
      (node (ref "RN3") (pin "5") (pinfunction "2_5") (pintype "passive"))
    )
    (net (code "39") (name "unconnected-(IC1-CBUS0-Pad22)") (class "Default")
      (node (ref "IC1") (pin "22") (pinfunction "CBUS0_22") (pintype "bidirectional"))
    )
    (net (code "40") (name "unconnected-(IC1-CBUS1-Pad21)") (class "Default")
      (node (ref "IC1") (pin "21") (pinfunction "CBUS1_21") (pintype "bidirectional"))
    )
    (net (code "41") (name "unconnected-(IC1-CBUS4-Pad9)") (class "Default")
      (node (ref "IC1") (pin "9") (pinfunction "CBUS4_9") (pintype "bidirectional"))
    )
    (net (code "42") (name "unconnected-(IC1-OSCI-Pad27)") (class "Default")
      (node (ref "IC1") (pin "27") (pinfunction "OSCI_27") (pintype "input"))
    )
    (net (code "43") (name "unconnected-(IC1-OSCO-Pad28)") (class "Default")
      (node (ref "IC1") (pin "28") (pinfunction "OSCO_28") (pintype "output"))
    )
    (net (code "44") (name "unconnected-(IC1-~{CTS}-Pad8)") (class "Default")
      (node (ref "IC1") (pin "8") (pinfunction "~{CTS}_8") (pintype "input"))
    )
    (net (code "45") (name "unconnected-(IC1-~{DCD}-Pad7)") (class "Default")
      (node (ref "IC1") (pin "7") (pinfunction "~{DCD}_7") (pintype "input"))
    )
    (net (code "46") (name "unconnected-(IC1-~{DSR}-Pad6)") (class "Default")
      (node (ref "IC1") (pin "6") (pinfunction "~{DSR}_6") (pintype "input"))
    )
    (net (code "47") (name "unconnected-(IC1-~{DTR}-Pad31)") (class "Default")
      (node (ref "IC1") (pin "31") (pinfunction "~{DTR}_31") (pintype "output"))
    )
    (net (code "48") (name "unconnected-(IC1-~{RESET}-Pad18)") (class "Default")
      (node (ref "IC1") (pin "18") (pinfunction "~{RESET}_18") (pintype "input"))
    )
    (net (code "49") (name "unconnected-(IC1-~{RI}-Pad3)") (class "Default")
      (node (ref "IC1") (pin "3") (pinfunction "~{RI}_3") (pintype "input"))
    )
    (net (code "50") (name "unconnected-(IC1-~{RTS}-Pad32)") (class "Default")
      (node (ref "IC1") (pin "32") (pinfunction "~{RTS}_32") (pintype "output"))
    )
    (net (code "51") (name "unconnected-(IC4-ADC1-Pad23)") (class "Default")
      (node (ref "IC4") (pin "23") (pinfunction "ADC1_23") (pintype "bidirectional"))
    )
    (net (code "52") (name "unconnected-(IC4-ADC2-Pad22)") (class "Default")
      (node (ref "IC4") (pin "22") (pinfunction "ADC2_22") (pintype "bidirectional"))
    )
    (net (code "53") (name "unconnected-(IC4-DIO0-Pad24)") (class "Default")
      (node (ref "IC4") (pin "24") (pinfunction "DIO0_24") (pintype "bidirectional"))
    )
    (net (code "54") (name "unconnected-(IC4-DIO1-Pad25)") (class "Default")
      (node (ref "IC4") (pin "25") (pinfunction "DIO1_25") (pintype "bidirectional"))
    )
    (net (code "55") (name "unconnected-(IC4-DIO2-Pad26)") (class "Default")
      (node (ref "IC4") (pin "26") (pinfunction "DIO2_26") (pintype "bidirectional"))
    )
    (net (code "56") (name "unconnected-(IC4-DIO3-Pad27)") (class "Default")
      (node (ref "IC4") (pin "27") (pinfunction "DIO3_27") (pintype "bidirectional"))
    )
    (net (code "57") (name "unconnected-(IC4-DIO12-Pad13)") (class "Default")
      (node (ref "IC4") (pin "13") (pinfunction "DIO12_13") (pintype "bidirectional"))
    )
    (net (code "58") (name "unconnected-(IC4-DIO16-Pad18)") (class "Default")
      (node (ref "IC4") (pin "18") (pinfunction "DIO16_18") (pintype "bidirectional"))
    )
    (net (code "59") (name "unconnected-(IC4-DIO17-Pad19)") (class "Default")
      (node (ref "IC4") (pin "19") (pinfunction "DIO17_19") (pintype "bidirectional"))
    )
    (net (code "60") (name "unconnected-(IC5-AUX_CL-Pad7)") (class "Default")
      (node (ref "IC5") (pin "7") (pinfunction "AUX_CL_7") (pintype "output"))
    )
    (net (code "61") (name "unconnected-(IC5-AUX_DA-Pad21)") (class "Default")
      (node (ref "IC5") (pin "21") (pinfunction "AUX_DA_21") (pintype "bidirectional"))
    )
    (net (code "62") (name "unconnected-(IC6-MISO-Pad6)") (class "Default")
      (node (ref "IC6") (pin "6") (pinfunction "MISO_6") (pintype "output"))
    )
    (net (code "63") (name "unconnected-(MODULE1-AIN-Pad10)") (class "Default")
      (node (ref "MODULE1") (pin "10") (pinfunction "AIN_10") (pintype "input"))
    )
    (net (code "64") (name "unconnected-(MODULE1-GPIO2{slash}RTS-Pad9)") (class "Default")
      (node (ref "MODULE1") (pin "9") (pinfunction "GPIO2/RTS_9") (pintype "bidirectional"))
    )
    (net (code "65") (name "unconnected-(MODULE1-GPIO3{slash}CTS-Pad7)") (class "Default")
      (node (ref "MODULE1") (pin "7") (pinfunction "GPIO3/CTS_7") (pintype "bidirectional"))
    )
    (net (code "66") (name "unconnected-(MODULE1-GPIO4-Pad5)") (class "Default")
      (node (ref "MODULE1") (pin "5") (pinfunction "GPIO4_5") (pintype "bidirectional"))
    )
    (net (code "67") (name "unconnected-(MODULE1-SPI_CLK-Pad14)") (class "Default")
      (node (ref "MODULE1") (pin "14") (pinfunction "SPI_CLK_14") (pintype "output"))
    )
    (net (code "68") (name "unconnected-(MODULE1-SPI_DI-Pad16)") (class "Default")
      (node (ref "MODULE1") (pin "16") (pinfunction "SPI_DI_16") (pintype "input"))
    )
    (net (code "69") (name "unconnected-(MODULE1-SPI_DO-Pad18)") (class "Default")
      (node (ref "MODULE1") (pin "18") (pinfunction "SPI_DO_18") (pintype "output"))
    )
    (net (code "70") (name "unconnected-(MODULE1-TOOL0-Pad1)") (class "Default")
      (node (ref "MODULE1") (pin "1") (pinfunction "TOOL0_1") (pintype "bidirectional"))
    )
    (net (code "71") (name "unconnected-(RN2-Pad1)") (class "Default")
      (node (ref "RN2") (pin "1") (pinfunction "1_1") (pintype "passive"))
    )
    (net (code "72") (name "unconnected-(RN2D-1-Pad4)") (class "Default")
      (node (ref "RN2") (pin "4") (pinfunction "1_4") (pintype "passive"))
    )
    (net (code "73") (name "unconnected-(SW1B-S-Pad3)") (class "Default")
      (node (ref "SW1") (pin "3") (pinfunction "S_3") (pintype "passive"))
    )
    (net (code "74") (name "unconnected-(X1-Pad4)") (class "Default")
      (node (ref "X1") (pin "4") (pinfunction "4_4") (pintype "passive"))
    )
  )
)
